# LedController.net
KiCad netlist of a schematic drawn in EAGLE
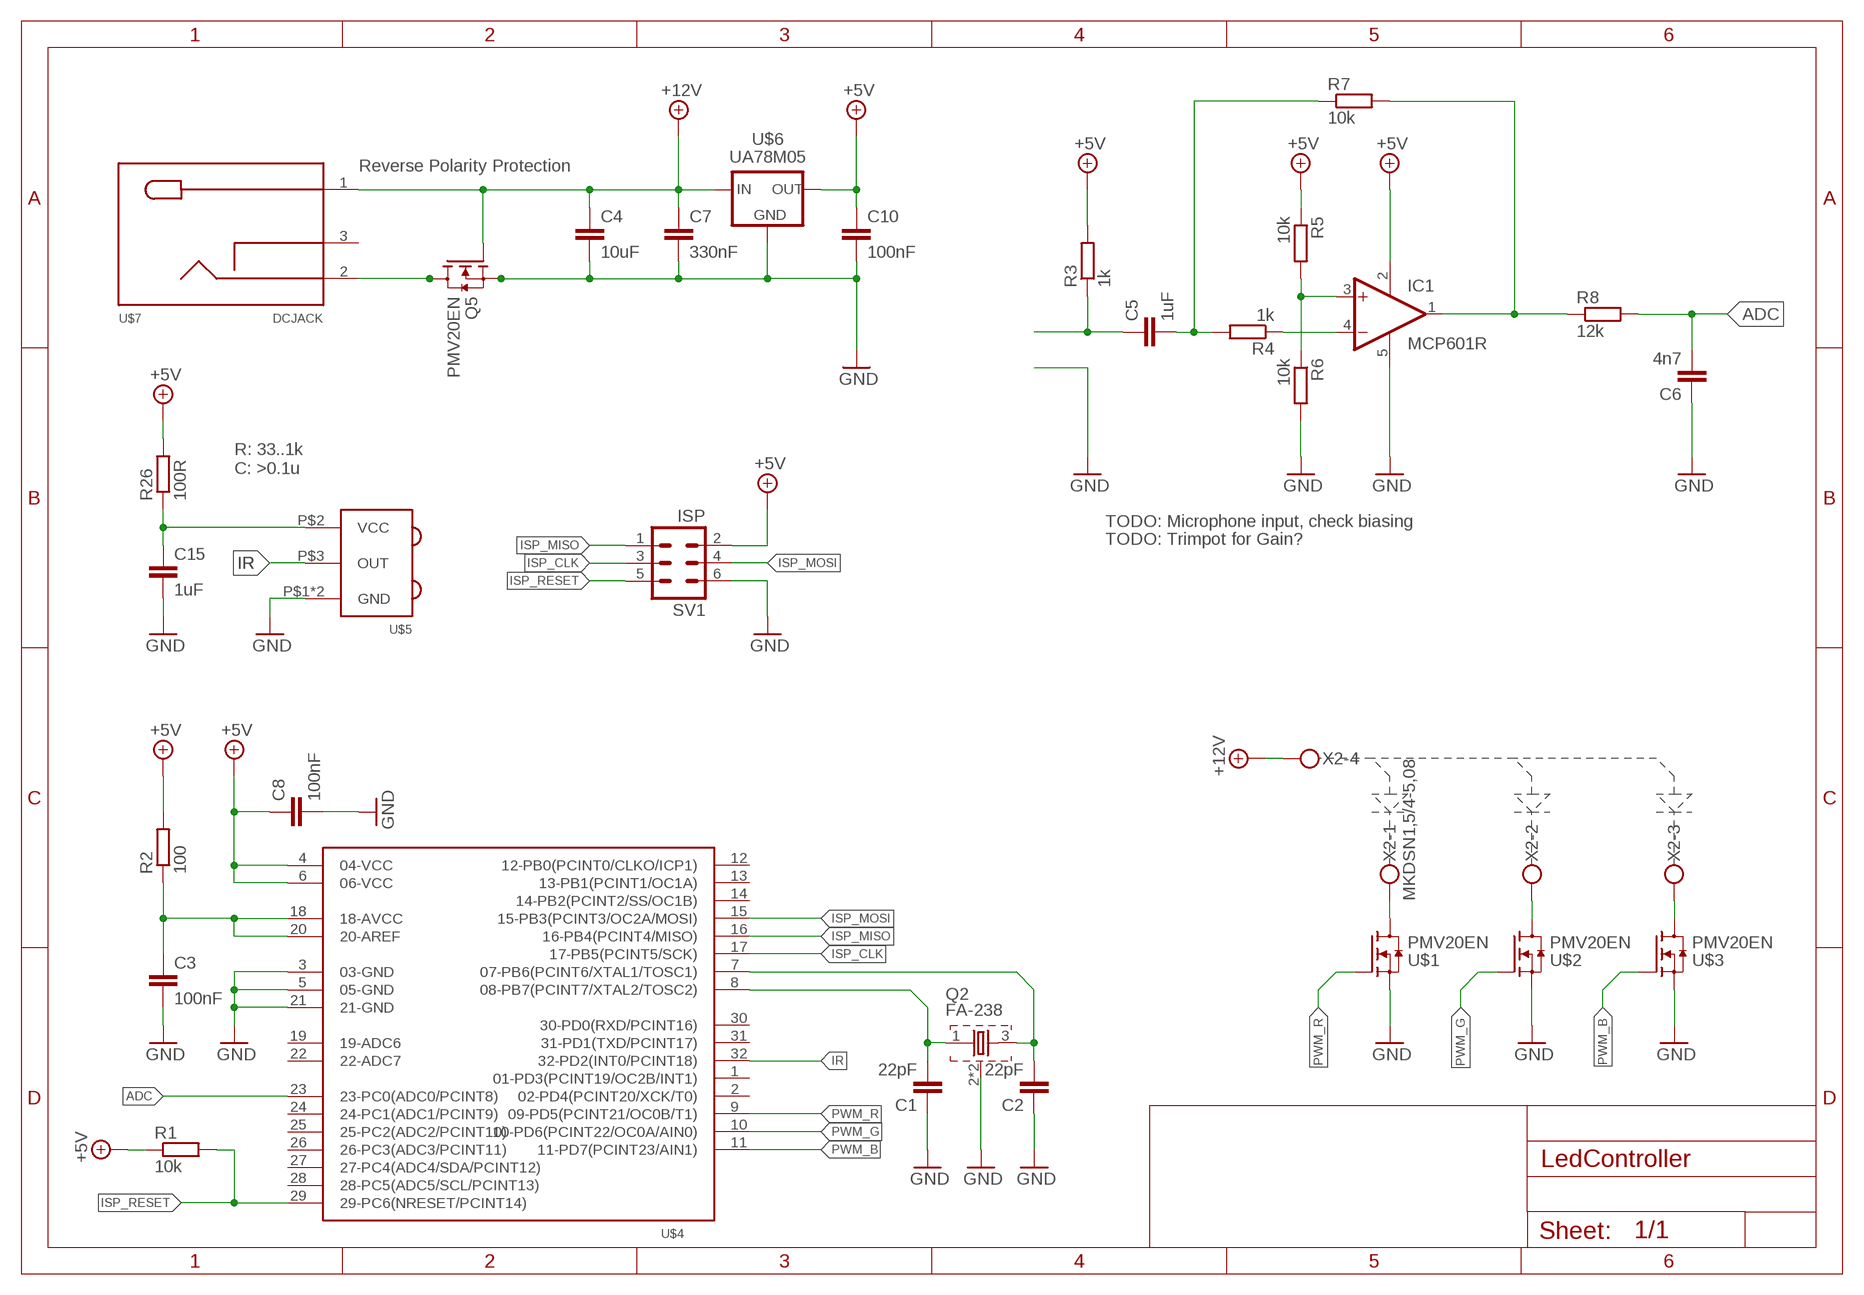
[diagram p0: schematic, sheet 1]

(export (version "E")
  (design (tool "Eeschema 10.0.6"))
  (components
    (comp (ref "C1")
      (value "22pF")
      (footprint "eagle-import:C0805")
      (libsource (lib "eagle-import") (part "C-EUC0805"))
    )
    (comp (ref "C2")
      (value "22pF")
      (footprint "eagle-import:C0805")
      (libsource (lib "eagle-import") (part "C-EUC0805"))
    )
    (comp (ref "C3")
      (value "100nF")
      (footprint "eagle-import:C0805")
      (libsource (lib "eagle-import") (part "C-EUC0805"))
    )
    (comp (ref "C4")
      (value "10uF")
      (footprint "eagle-import:C0805")
      (libsource (lib "eagle-import") (part "C-EUC0805"))
    )
    (comp (ref "C5")
      (value "1uF")
      (footprint "eagle-import:C0805")
      (libsource (lib "eagle-import") (part "C-EUC0805"))
    )
    (comp (ref "C6")
      (value "4n7")
      (footprint "eagle-import:C0805")
      (libsource (lib "eagle-import") (part "C-EUC0805"))
    )
    (comp (ref "C7")
      (value "330nF")
      (footprint "eagle-import:C0805")
      (libsource (lib "eagle-import") (part "C-EUC0805"))
    )
    (comp (ref "C8")
      (value "100nF")
      (footprint "eagle-import:C0805")
      (libsource (lib "eagle-import") (part "C-EUC0805"))
    )
    (comp (ref "C10")
      (value "100nF")
      (footprint "eagle-import:C0805")
      (libsource (lib "eagle-import") (part "C-EUC0805"))
    )
    (comp (ref "C15")
      (value "1uF")
      (footprint "eagle-import:C0805")
      (libsource (lib "eagle-import") (part "C-EUC0805"))
    )
    (comp (ref "IC1")
      (value "MCP601R")
      (footprint "eagle-import:SOT23-5")
      (libsource (lib "eagle-import") (part "MCP601R"))
    )
    (comp (ref "Q2")
      (value "FA-238")
      (footprint "eagle-import:FA-238")
      (libsource (lib "eagle-import") (part "FA-238"))
    )
    (comp (ref "Q5")
      (value "PMV20EN")
      (footprint "eagle-import:SOT23")
      (libsource (lib "eagle-import") (part "PMV20EN"))
    )
    (comp (ref "R1")
      (value "10k")
      (footprint "eagle-import:R0805")
      (libsource (lib "eagle-import") (part "R-EU_R0805"))
    )
    (comp (ref "R2")
      (value "100")
      (footprint "eagle-import:R0805")
      (libsource (lib "eagle-import") (part "R-EU_R0805"))
    )
    (comp (ref "R3")
      (value "1k")
      (footprint "eagle-import:M0805")
      (libsource (lib "eagle-import") (part "R-EU_M0805"))
    )
    (comp (ref "R4")
      (value "1k")
      (footprint "eagle-import:R0805")
      (libsource (lib "eagle-import") (part "R-EU_R0805"))
    )
    (comp (ref "R5")
      (value "10k")
      (footprint "eagle-import:R0805")
      (libsource (lib "eagle-import") (part "R-EU_R0805"))
    )
    (comp (ref "R6")
      (value "10k")
      (footprint "eagle-import:R0805")
      (libsource (lib "eagle-import") (part "R-EU_R0805"))
    )
    (comp (ref "R7")
      (value "10k")
      (footprint "eagle-import:R0805")
      (libsource (lib "eagle-import") (part "R-EU_R0805"))
    )
    (comp (ref "R8")
      (value "12k")
      (footprint "eagle-import:R0805")
      (libsource (lib "eagle-import") (part "R-EU_R0805"))
    )
    (comp (ref "R26")
      (value "100R")
      (footprint "eagle-import:R0805")
      (libsource (lib "eagle-import") (part "R-EU_R0805"))
    )
    (comp (ref "SV1")
      (value "ISP")
      (footprint "eagle-import:MA03-2")
      (libsource (lib "eagle-import") (part "MA03-2"))
    )
    (comp (ref "U$1")
      (value "PMV20EN")
      (footprint "eagle-import:SOT23")
      (libsource (lib "eagle-import") (part "PMV20EN"))
    )
    (comp (ref "U$2")
      (value "PMV20EN")
      (footprint "eagle-import:SOT23")
      (libsource (lib "eagle-import") (part "PMV20EN"))
    )
    (comp (ref "U$3")
      (value "PMV20EN")
      (footprint "eagle-import:SOT23")
      (libsource (lib "eagle-import") (part "PMV20EN"))
    )
    (comp (ref "U$4")
      (value "ATMEGA328")
      (footprint "eagle-import:TQFP32")
      (libsource (lib "eagle-import") (part "ATMEGA328"))
    )
    (comp (ref "U$5")
      (value "TSOP75236")
      (footprint "eagle-import:TSOP75236")
      (libsource (lib "eagle-import") (part "TSOP75236"))
    )
    (comp (ref "U$6")
      (value "UA78M05")
      (footprint "eagle-import:SOT-223")
      (libsource (lib "eagle-import") (part "UA78M05"))
    )
    (comp (ref "U$7")
      (value "DCJACK")
      (footprint "eagle-import:DCJACK")
      (libsource (lib "eagle-import") (part "DCJACK"))
    )
    (comp (ref "X2")
      (value "MKDSN1,5/4-5,08")
      (footprint "eagle-import:MKDSN1,5_4-5,08")
      (libsource (lib "eagle-import") (part "MKDSN1,5/4-5,08"))
    )
  )
  (nets
    (net (code "1") (name "+5V") (class "Default")
      (node (ref "C10") (pin "1") (pinfunction "1_1") (pintype "passive"))
      (node (ref "C8") (pin "1") (pinfunction "1_1") (pintype "passive"))
      (node (ref "IC1") (pin "2") (pinfunction "V+_2") (pintype "power_in"))
      (node (ref "R1") (pin "1") (pinfunction "1_1") (pintype "passive"))
      (node (ref "R2") (pin "2") (pinfunction "2_2") (pintype "passive"))
      (node (ref "R26") (pin "2") (pinfunction "2_2") (pintype "passive"))
      (node (ref "R3") (pin "2") (pinfunction "2_2") (pintype "passive"))
      (node (ref "R5") (pin "1") (pinfunction "1_1") (pintype "passive"))
      (node (ref "SV1") (pin "2") (pinfunction "2_2") (pintype "passive"))
      (node (ref "U$4") (pin "4") (pinfunction "04-VCC_4") (pintype "bidirectional"))
      (node (ref "U$4") (pin "6") (pinfunction "06-VCC_6") (pintype "bidirectional"))
      (node (ref "U$6") (pin "3") (pinfunction "OUT_3") (pintype "passive"))
    )
    (net (code "2") (name "+12V") (class "Default")
      (node (ref "C4") (pin "1") (pinfunction "1_1") (pintype "passive"))
      (node (ref "C7") (pin "1") (pinfunction "1_1") (pintype "passive"))
      (node (ref "Q5") (pin "1") (pinfunction "G_1") (pintype "passive"))
      (node (ref "U$6") (pin "1") (pinfunction "IN_1") (pintype "input"))
      (node (ref "U$7") (pin "1") (pinfunction "1_1") (pintype "bidirectional"))
      (node (ref "X2") (pin "4") (pinfunction "KL_4") (pintype "passive"))
    )
    (net (code "3") (name "ADC") (class "Default")
      (node (ref "C6") (pin "2") (pinfunction "2_2") (pintype "passive"))
      (node (ref "R8") (pin "2") (pinfunction "2_2") (pintype "passive"))
      (node (ref "U$4") (pin "23") (pinfunction "23-PC0(ADC0/PCINT8)_23") (pintype "bidirectional"))
    )
    (net (code "4") (name "GND") (class "Default")
      (node (ref "C1") (pin "1") (pinfunction "1_1") (pintype "passive"))
      (node (ref "C10") (pin "2") (pinfunction "2_2") (pintype "passive"))
      (node (ref "C15") (pin "2") (pinfunction "2_2") (pintype "passive"))
      (node (ref "C2") (pin "1") (pinfunction "1_1") (pintype "passive"))
      (node (ref "C3") (pin "2") (pinfunction "2_2") (pintype "passive"))
      (node (ref "C4") (pin "2") (pinfunction "2_2") (pintype "passive"))
      (node (ref "C6") (pin "1") (pinfunction "1_1") (pintype "passive"))
      (node (ref "C7") (pin "2") (pinfunction "2_2") (pintype "passive"))
      (node (ref "C8") (pin "2") (pinfunction "2_2") (pintype "passive"))
      (node (ref "IC1") (pin "5") (pinfunction "V-_5") (pintype "power_in"))
      (node (ref "Q2") (pin "2") (pinfunction "2_2") (pintype "passive"))
      (node (ref "Q2") (pin "4") (pinfunction "2_4") (pintype "passive"))
      (node (ref "Q5") (pin "2") (pinfunction "S_2") (pintype "passive"))
      (node (ref "R6") (pin "2") (pinfunction "2_2") (pintype "passive"))
      (node (ref "SV1") (pin "6") (pinfunction "6_6") (pintype "passive"))
      (node (ref "U$1") (pin "2") (pinfunction "S_2") (pintype "passive"))
      (node (ref "U$2") (pin "2") (pinfunction "S_2") (pintype "passive"))
      (node (ref "U$3") (pin "2") (pinfunction "S_2") (pintype "passive"))
      (node (ref "U$4") (pin "21") (pinfunction "21-GND_21") (pintype "bidirectional"))
      (node (ref "U$4") (pin "3") (pinfunction "03-GND_3") (pintype "bidirectional"))
      (node (ref "U$4") (pin "5") (pinfunction "05-GND_5") (pintype "bidirectional"))
      (node (ref "U$5") (pin "P$1") (pinfunction "GND_P$1") (pintype "power_in"))
      (node (ref "U$5") (pin "P$4") (pinfunction "GND_P$4") (pintype "power_in"))
      (node (ref "U$6") (pin "2") (pinfunction "GND_2") (pintype "input"))
      (node (ref "U$6") (pin "TER") (pinfunction "GND_TER") (pintype "input"))
    )
    (net (code "5") (name "IR") (class "Default")
      (node (ref "U$4") (pin "32") (pinfunction "32-PD2(INT0/PCINT18)_32") (pintype "bidirectional"))
      (node (ref "U$5") (pin "P$3") (pinfunction "OUT_P$3") (pintype "output"))
    )
    (net (code "6") (name "ISP_CLK") (class "Default")
      (node (ref "SV1") (pin "3") (pinfunction "3_3") (pintype "passive"))
      (node (ref "U$4") (pin "17") (pinfunction "17-PB5(PCINT5/SCK)_17") (pintype "bidirectional"))
    )
    (net (code "7") (name "ISP_MISO") (class "Default")
      (node (ref "SV1") (pin "1") (pinfunction "1_1") (pintype "passive"))
      (node (ref "U$4") (pin "16") (pinfunction "16-PB4(PCINT4/MISO)_16") (pintype "bidirectional"))
    )
    (net (code "8") (name "ISP_MOSI") (class "Default")
      (node (ref "SV1") (pin "4") (pinfunction "4_4") (pintype "passive"))
      (node (ref "U$4") (pin "15") (pinfunction "15-PB3(PCINT3/OC2A/MOSI)_15") (pintype "bidirectional"))
    )
    (net (code "9") (name "ISP_RESET") (class "Default")
      (node (ref "R1") (pin "2") (pinfunction "2_2") (pintype "passive"))
      (node (ref "SV1") (pin "5") (pinfunction "5_5") (pintype "passive"))
      (node (ref "U$4") (pin "29") (pinfunction "29-PC6(NRESET/PCINT14)_29") (pintype "bidirectional"))
    )
    (net (code "10") (name "Net-(C5-Pad1)") (class "Default")
      (node (ref "C5") (pin "1") (pinfunction "1_1") (pintype "passive"))
      (node (ref "R3") (pin "1") (pinfunction "1_1") (pintype "passive"))
    )
    (net (code "11") (name "Net-(C5-Pad2)") (class "Default")
      (node (ref "C5") (pin "2") (pinfunction "2_2") (pintype "passive"))
      (node (ref "R4") (pin "2") (pinfunction "2_2") (pintype "passive"))
      (node (ref "R7") (pin "1") (pinfunction "1_1") (pintype "passive"))
    )
    (net (code "12") (name "Net-(IC1-+IN)") (class "Default")
      (node (ref "IC1") (pin "3") (pinfunction "+IN_3") (pintype "input"))
      (node (ref "R5") (pin "2") (pinfunction "2_2") (pintype "passive"))
      (node (ref "R6") (pin "1") (pinfunction "1_1") (pintype "passive"))
    )
    (net (code "13") (name "Net-(IC1--IN)") (class "Default")
      (node (ref "IC1") (pin "4") (pinfunction "-IN_4") (pintype "input"))
      (node (ref "R4") (pin "1") (pinfunction "1_1") (pintype "passive"))
    )
    (net (code "14") (name "Net-(IC1-OUT)") (class "Default")
      (node (ref "IC1") (pin "1") (pinfunction "OUT_1") (pintype "output"))
      (node (ref "R7") (pin "2") (pinfunction "2_2") (pintype "passive"))
      (node (ref "R8") (pin "1") (pinfunction "1_1") (pintype "passive"))
    )
    (net (code "15") (name "Net-(Q5-D)") (class "Default")
      (node (ref "Q5") (pin "3") (pinfunction "D_3") (pintype "passive"))
      (node (ref "U$7") (pin "2") (pinfunction "2_2") (pintype "bidirectional"))
    )
    (net (code "16") (name "Net-(U$1-D)") (class "Default")
      (node (ref "U$1") (pin "3") (pinfunction "D_3") (pintype "passive"))
      (node (ref "X2") (pin "1") (pinfunction "KL_1") (pintype "passive"))
    )
    (net (code "17") (name "Net-(U$2-D)") (class "Default")
      (node (ref "U$2") (pin "3") (pinfunction "D_3") (pintype "passive"))
      (node (ref "X2") (pin "2") (pinfunction "KL_2") (pintype "passive"))
    )
    (net (code "18") (name "Net-(U$3-D)") (class "Default")
      (node (ref "U$3") (pin "3") (pinfunction "D_3") (pintype "passive"))
      (node (ref "X2") (pin "3") (pinfunction "KL_3") (pintype "passive"))
    )
    (net (code "19") (name "Net-(U$4-07-PB6(PCINT6{slash}XTAL1{slash}TOSC1))") (class "Default")
      (node (ref "C2") (pin "2") (pinfunction "2_2") (pintype "passive"))
      (node (ref "Q2") (pin "3") (pinfunction "3_3") (pintype "passive"))
      (node (ref "U$4") (pin "7") (pinfunction "07-PB6(PCINT6/XTAL1/TOSC1)_7") (pintype "bidirectional"))
    )
    (net (code "20") (name "Net-(U$4-08-PB7(PCINT7{slash}XTAL2{slash}TOSC2))") (class "Default")
      (node (ref "C1") (pin "2") (pinfunction "2_2") (pintype "passive"))
      (node (ref "Q2") (pin "1") (pinfunction "1_1") (pintype "passive"))
      (node (ref "U$4") (pin "8") (pinfunction "08-PB7(PCINT7/XTAL2/TOSC2)_8") (pintype "bidirectional"))
    )
    (net (code "21") (name "Net-(U$4-18-AVCC)") (class "Default")
      (node (ref "C3") (pin "1") (pinfunction "1_1") (pintype "passive"))
      (node (ref "R2") (pin "1") (pinfunction "1_1") (pintype "passive"))
      (node (ref "U$4") (pin "18") (pinfunction "18-AVCC_18") (pintype "bidirectional"))
      (node (ref "U$4") (pin "20") (pinfunction "20-AREF_20") (pintype "bidirectional"))
    )
    (net (code "22") (name "Net-(U$5-VCC)") (class "Default")
      (node (ref "C15") (pin "1") (pinfunction "1_1") (pintype "passive"))
      (node (ref "R26") (pin "1") (pinfunction "1_1") (pintype "passive"))
      (node (ref "U$5") (pin "P$2") (pinfunction "VCC_P$2") (pintype "power_in"))
    )
    (net (code "23") (name "PWM_B") (class "Default")
      (node (ref "U$3") (pin "1") (pinfunction "G_1") (pintype "passive"))
      (node (ref "U$4") (pin "11") (pinfunction "11-PD7(PCINT23/AIN1)_11") (pintype "bidirectional"))
    )
    (net (code "24") (name "PWM_G") (class "Default")
      (node (ref "U$2") (pin "1") (pinfunction "G_1") (pintype "passive"))
      (node (ref "U$4") (pin "10") (pinfunction "10-PD6(PCINT22/OC0A/AIN0)_10") (pintype "bidirectional"))
    )
    (net (code "25") (name "PWM_R") (class "Default")
      (node (ref "U$1") (pin "1") (pinfunction "G_1") (pintype "passive"))
      (node (ref "U$4") (pin "9") (pinfunction "09-PD5(PCINT21/OC0B/T1)_9") (pintype "bidirectional"))
    )
    (net (code "26") (name "unconnected-(U$4-01-PD3(PCINT19{slash}OC2B{slash}INT1)-Pad1)") (class "Default")
      (node (ref "U$4") (pin "1") (pinfunction "01-PD3(PCINT19/OC2B/INT1)_1") (pintype "bidirectional"))
    )
    (net (code "27") (name "unconnected-(U$4-02-PD4(PCINT20{slash}XCK{slash}T0)-Pad2)") (class "Default")
      (node (ref "U$4") (pin "2") (pinfunction "02-PD4(PCINT20/XCK/T0)_2") (pintype "bidirectional"))
    )
    (net (code "28") (name "unconnected-(U$4-12-PB0(PCINT0{slash}CLKO{slash}ICP1)-Pad12)") (class "Default")
      (node (ref "U$4") (pin "12") (pinfunction "12-PB0(PCINT0/CLKO/ICP1)_12") (pintype "bidirectional"))
    )
    (net (code "29") (name "unconnected-(U$4-13-PB1(PCINT1{slash}OC1A)-Pad13)") (class "Default")
      (node (ref "U$4") (pin "13") (pinfunction "13-PB1(PCINT1/OC1A)_13") (pintype "bidirectional"))
    )
    (net (code "30") (name "unconnected-(U$4-14-PB2(PCINT2{slash}SS{slash}OC1B)-Pad14)") (class "Default")
      (node (ref "U$4") (pin "14") (pinfunction "14-PB2(PCINT2/SS/OC1B)_14") (pintype "bidirectional"))
    )
    (net (code "31") (name "unconnected-(U$4-19-ADC6-Pad19)") (class "Default")
      (node (ref "U$4") (pin "19") (pinfunction "19-ADC6_19") (pintype "bidirectional"))
    )
    (net (code "32") (name "unconnected-(U$4-22-ADC7-Pad22)") (class "Default")
      (node (ref "U$4") (pin "22") (pinfunction "22-ADC7_22") (pintype "bidirectional"))
    )
    (net (code "33") (name "unconnected-(U$4-24-PC1(ADC1{slash}PCINT9)-Pad24)") (class "Default")
      (node (ref "U$4") (pin "24") (pinfunction "24-PC1(ADC1/PCINT9)_24") (pintype "bidirectional"))
    )
    (net (code "34") (name "unconnected-(U$4-25-PC2(ADC2{slash}PCINT10)-Pad25)") (class "Default")
      (node (ref "U$4") (pin "25") (pinfunction "25-PC2(ADC2/PCINT10)_25") (pintype "bidirectional"))
    )
    (net (code "35") (name "unconnected-(U$4-26-PC3(ADC3{slash}PCINT11)-Pad26)") (class "Default")
      (node (ref "U$4") (pin "26") (pinfunction "26-PC3(ADC3/PCINT11)_26") (pintype "bidirectional"))
    )
    (net (code "36") (name "unconnected-(U$4-27-PC4(ADC4{slash}SDA{slash}PCINT12)-Pad27)") (class "Default")
      (node (ref "U$4") (pin "27") (pinfunction "27-PC4(ADC4/SDA/PCINT12)_27") (pintype "bidirectional"))
    )
    (net (code "37") (name "unconnected-(U$4-28-PC5(ADC5{slash}SCL{slash}PCINT13)-Pad28)") (class "Default")
      (node (ref "U$4") (pin "28") (pinfunction "28-PC5(ADC5/SCL/PCINT13)_28") (pintype "bidirectional"))
    )
    (net (code "38") (name "unconnected-(U$4-30-PD0(RXD{slash}PCINT16)-Pad30)") (class "Default")
      (node (ref "U$4") (pin "30") (pinfunction "30-PD0(RXD/PCINT16)_30") (pintype "bidirectional"))
    )
    (net (code "39") (name "unconnected-(U$4-31-PD1(TXD{slash}PCINT17)-Pad31)") (class "Default")
      (node (ref "U$4") (pin "31") (pinfunction "31-PD1(TXD/PCINT17)_31") (pintype "bidirectional"))
    )
    (net (code "40") (name "unconnected-(U$7-Pad3)") (class "Default")
      (node (ref "U$7") (pin "3") (pinfunction "3_3") (pintype "bidirectional"))
    )
  )
)
